# Encoder.net
KiCad netlist of a schematic drawn in EAGLE
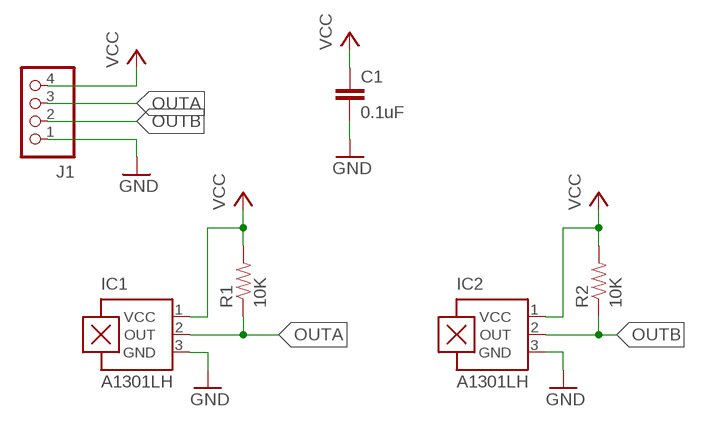
[diagram p0: schematic, sheet 1]

(export (version "E")
  (design (tool "Eeschema 10.0.6"))
  (components
    (comp (ref "C1")
      (value "0.1uF")
      (footprint "eagle-import:0603-CAP")
      (libsource (lib "eagle-import") (part "CAP0603-CAP"))
    )
    (comp (ref "IC1")
      (value "A1301LH")
      (footprint "eagle-import:SOT23-W")
      (fields (field (name "MF") "ALLEGRO MICROSYSTEMS, INC.") (field (name "MPN") "A1301ELHLT-T"))
      (libsource (lib "eagle-import") (part "A13?LH01"))
    )
    (comp (ref "IC2")
      (value "A1301LH")
      (footprint "eagle-import:SOT23-W")
      (fields (field (name "MF") "ALLEGRO MICROSYSTEMS, INC.") (field (name "MPN") "A1301ELHLT-T"))
      (libsource (lib "eagle-import") (part "A13?LH01"))
    )
    (comp (ref "J1")
      (value "B4B-PH-K-S")
      (footprint "eagle-import:B4B-PH-K-S")
      (libsource (lib "eagle-import") (part "B4B-PH-K-S"))
    )
    (comp (ref "R1")
      (value "10K")
      (footprint "eagle-import:0603-RES")
      (libsource (lib "eagle-import") (part "RESISTOR0603"))
    )
    (comp (ref "R2")
      (value "10K")
      (footprint "eagle-import:0603-RES")
      (libsource (lib "eagle-import") (part "RESISTOR0603"))
    )
  )
  (nets
    (net (code "1") (name "GND") (class "Default")
      (node (ref "C1") (pin "2") (pinfunction "2_2") (pintype "passive"))
      (node (ref "IC1") (pin "3") (pinfunction "GND_3") (pintype "power_in"))
      (node (ref "IC2") (pin "3") (pinfunction "GND_3") (pintype "power_in"))
      (node (ref "J1") (pin "1") (pinfunction "1_1") (pintype "passive"))
    )
    (net (code "2") (name "OUTA") (class "Default")
      (node (ref "IC1") (pin "2") (pinfunction "OUT_2") (pintype "output"))
      (node (ref "J1") (pin "3") (pinfunction "3_3") (pintype "passive"))
      (node (ref "R1") (pin "1") (pinfunction "1_1") (pintype "passive"))
    )
    (net (code "3") (name "OUTB") (class "Default")
      (node (ref "IC2") (pin "2") (pinfunction "OUT_2") (pintype "output"))
      (node (ref "J1") (pin "2") (pinfunction "2_2") (pintype "passive"))
      (node (ref "R2") (pin "1") (pinfunction "1_1") (pintype "passive"))
    )
    (net (code "4") (name "VCC") (class "Default")
      (node (ref "C1") (pin "1") (pinfunction "1_1") (pintype "passive"))
      (node (ref "IC1") (pin "1") (pinfunction "VCC_1") (pintype "power_in"))
      (node (ref "IC2") (pin "1") (pinfunction "VCC_1") (pintype "power_in"))
      (node (ref "J1") (pin "4") (pinfunction "4_4") (pintype "passive"))
      (node (ref "R1") (pin "2") (pinfunction "2_2") (pintype "passive"))
      (node (ref "R2") (pin "2") (pinfunction "2_2") (pintype "passive"))
    )
  )
)
